# dice.net
KiCad netlist of a schematic drawn in EAGLE
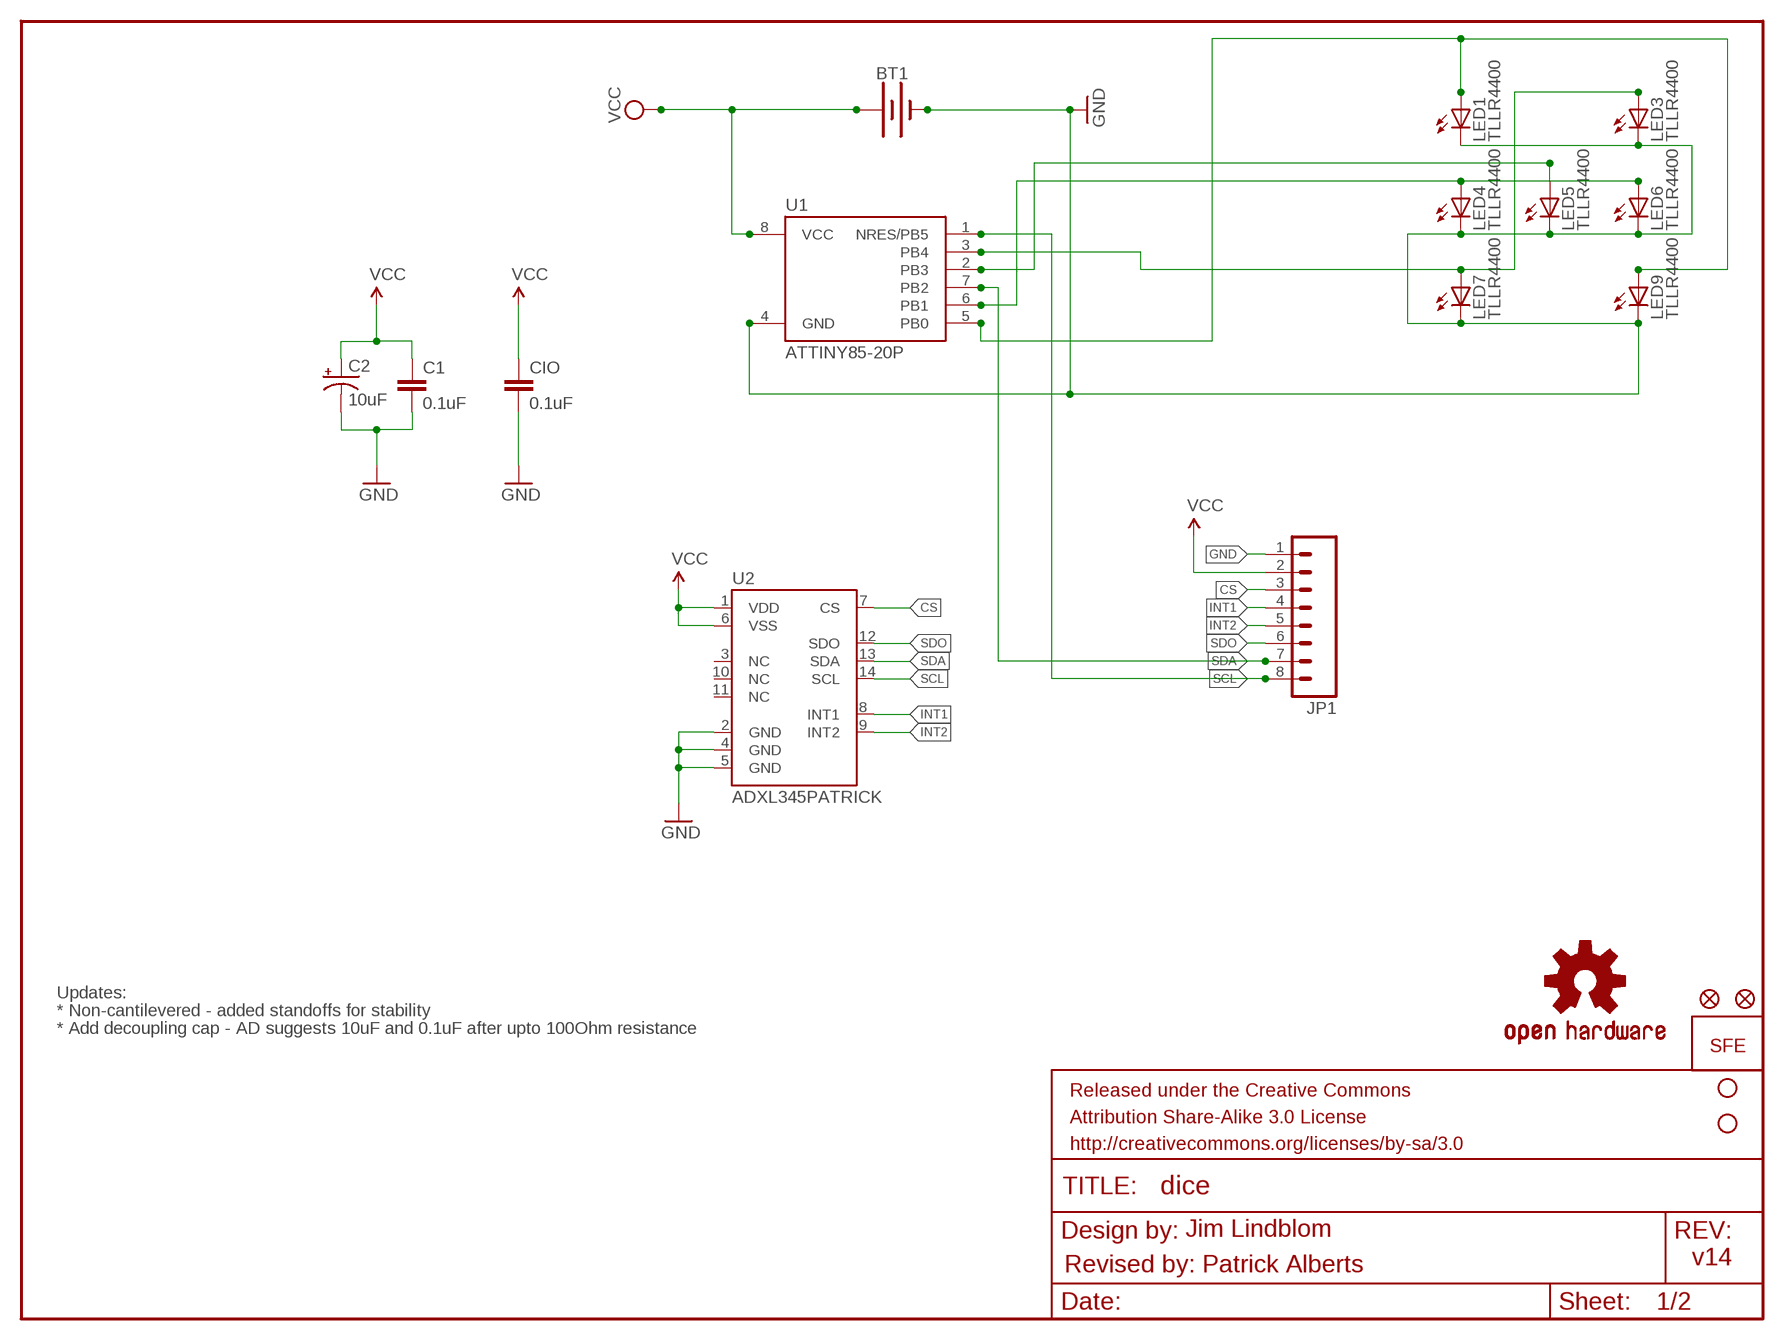
[diagram p0: schematic, sheet 1]

(export (version "E")
  (design (tool "Eeschema 10.0.6"))
  (components
    (comp (ref "BT1")
      (value "BATTERY-20MM_PTH")
      (footprint "eagle-import:BATTCOM_20MM_PTH")
      (libsource (lib "eagle-import") (part "BATTERY-20MM_PTH"))
    )
    (comp (ref "C1")
      (value "0.1uF")
      (footprint "eagle-import:0603-CAP")
      (libsource (lib "eagle-import") (part "CAP0603-CAP"))
    )
    (comp (ref "C2")
      (value "10uF")
      (footprint "eagle-import:EIA3216")
      (libsource (lib "eagle-import") (part "CAP_POL1206"))
    )
    (comp (ref "CIO")
      (value "0.1uF")
      (footprint "eagle-import:0603-CAP")
      (libsource (lib "eagle-import") (part "CAP0603-CAP"))
    )
    (comp (ref "JP1")
      (value "M08")
      (footprint "eagle-import:1X08")
      (libsource (lib "eagle-import") (part "M08"))
    )
    (comp (ref "JP2")
      (value "STAND-OFF")
      (footprint "eagle-import:STAND-OFF")
      (libsource (lib "eagle-import") (part "STAND-OFF"))
    )
    (comp (ref "JP3")
      (value "STAND-OFF")
      (footprint "eagle-import:STAND-OFF")
      (libsource (lib "eagle-import") (part "STAND-OFF"))
    )
    (comp (ref "JP4")
      (value "FIDUCIAL1X2")
      (footprint "eagle-import:FIDUCIAL-1X2")
      (libsource (lib "eagle-import") (part "FIDUCIAL1X2"))
    )
    (comp (ref "JP5")
      (value "FIDUCIAL1X2")
      (footprint "eagle-import:FIDUCIAL-1X2")
      (libsource (lib "eagle-import") (part "FIDUCIAL1X2"))
    )
    (comp (ref "LED1")
      (value "TLLR4400")
      (footprint "eagle-import:LED3MM")
      (fields (field (name "MF") "VISHAY SEMICONDUCTOR"))
      (libsource (lib "eagle-import") (part "TLLR4400"))
    )
    (comp (ref "LED3")
      (value "TLLR4400")
      (footprint "eagle-import:LED3MM")
      (fields (field (name "MF") "VISHAY SEMICONDUCTOR"))
      (libsource (lib "eagle-import") (part "TLLR4400"))
    )
    (comp (ref "LED4")
      (value "TLLR4400")
      (footprint "eagle-import:LED3MM")
      (fields (field (name "MF") "VISHAY SEMICONDUCTOR"))
      (libsource (lib "eagle-import") (part "TLLR4400"))
    )
    (comp (ref "LED5")
      (value "TLLR4400")
      (footprint "eagle-import:LED3MM")
      (fields (field (name "MF") "VISHAY SEMICONDUCTOR"))
      (libsource (lib "eagle-import") (part "TLLR4400"))
    )
    (comp (ref "LED6")
      (value "TLLR4400")
      (footprint "eagle-import:LED3MM")
      (fields (field (name "MF") "VISHAY SEMICONDUCTOR"))
      (libsource (lib "eagle-import") (part "TLLR4400"))
    )
    (comp (ref "LED7")
      (value "TLLR4400")
      (footprint "eagle-import:LED3MM")
      (fields (field (name "MF") "VISHAY SEMICONDUCTOR"))
      (libsource (lib "eagle-import") (part "TLLR4400"))
    )
    (comp (ref "LED9")
      (value "TLLR4400")
      (footprint "eagle-import:LED3MM")
      (fields (field (name "MF") "VISHAY SEMICONDUCTOR"))
      (libsource (lib "eagle-import") (part "TLLR4400"))
    )
    (comp (ref "U$2")
      (value "LOGO-SFENEW")
      (footprint "eagle-import:SFE-NEW-WEBLOGO")
      (libsource (lib "eagle-import") (part "LOGO-SFENEW"))
    )
    (comp (ref "U$3")
      (value "OSHW-LOGOS")
      (footprint "eagle-import:OSHW-LOGO-S")
      (libsource (lib "eagle-import") (part "OSHW-LOGOS"))
    )
    (comp (ref "U1")
      (value "ATTINY85-20P")
      (footprint "eagle-import:PDIP08_300MIL")
      (libsource (lib "eagle-import") (part "ATTINY85P-20"))
    )
    (comp (ref "U2")
      (value "ADXL345PATRICK")
      (footprint "eagle-import:LGA14_1_1_PATRICK")
      (libsource (lib "eagle-import") (part "ADXL345PATRICK"))
    )
  )
  (nets
    (net (code "1") (name "CS") (class "Default")
      (node (ref "JP1") (pin "3") (pinfunction "3_3") (pintype "passive"))
      (node (ref "U2") (pin "7") (pinfunction "CS_7") (pintype "bidirectional"))
    )
    (net (code "2") (name "GND") (class "Default")
      (node (ref "BT1") (pin "2") (pinfunction "-_2") (pintype "power_in"))
      (node (ref "C1") (pin "2") (pinfunction "2_2") (pintype "passive"))
      (node (ref "C2") (pin "C") (pinfunction "-_C") (pintype "passive"))
      (node (ref "CIO") (pin "2") (pinfunction "2_2") (pintype "passive"))
      (node (ref "JP1") (pin "1") (pinfunction "1_1") (pintype "passive"))
      (node (ref "LED1") (pin "K") (pinfunction "C_K") (pintype "passive"))
      (node (ref "LED3") (pin "K") (pinfunction "C_K") (pintype "passive"))
      (node (ref "LED4") (pin "K") (pinfunction "C_K") (pintype "passive"))
      (node (ref "LED5") (pin "K") (pinfunction "C_K") (pintype "passive"))
      (node (ref "LED6") (pin "K") (pinfunction "C_K") (pintype "passive"))
      (node (ref "LED7") (pin "K") (pinfunction "C_K") (pintype "passive"))
      (node (ref "LED9") (pin "K") (pinfunction "C_K") (pintype "passive"))
      (node (ref "U1") (pin "4") (pinfunction "GND_4") (pintype "power_in"))
      (node (ref "U2") (pin "2") (pinfunction "GND_2") (pintype "bidirectional"))
      (node (ref "U2") (pin "4") (pinfunction "GND_4") (pintype "bidirectional"))
      (node (ref "U2") (pin "5") (pinfunction "GND_5") (pintype "bidirectional"))
    )
    (net (code "3") (name "INT1") (class "Default")
      (node (ref "JP1") (pin "4") (pinfunction "4_4") (pintype "passive"))
      (node (ref "U2") (pin "8") (pinfunction "INT1_8") (pintype "bidirectional"))
    )
    (net (code "4") (name "INT2") (class "Default")
      (node (ref "JP1") (pin "5") (pinfunction "5_5") (pintype "passive"))
      (node (ref "U2") (pin "9") (pinfunction "INT2_9") (pintype "bidirectional"))
    )
    (net (code "5") (name "Net-(U1-PB0)") (class "Default")
      (node (ref "LED1") (pin "A") (pinfunction "A_A") (pintype "passive"))
      (node (ref "LED9") (pin "A") (pinfunction "A_A") (pintype "passive"))
      (node (ref "U1") (pin "5") (pinfunction "PB0_5") (pintype "bidirectional"))
    )
    (net (code "6") (name "Net-(U1-PB1)") (class "Default")
      (node (ref "LED4") (pin "A") (pinfunction "A_A") (pintype "passive"))
      (node (ref "LED6") (pin "A") (pinfunction "A_A") (pintype "passive"))
      (node (ref "U1") (pin "6") (pinfunction "PB1_6") (pintype "bidirectional"))
    )
    (net (code "7") (name "Net-(U1-PB3)") (class "Default")
      (node (ref "LED5") (pin "A") (pinfunction "A_A") (pintype "passive"))
      (node (ref "U1") (pin "2") (pinfunction "PB3_2") (pintype "bidirectional"))
    )
    (net (code "8") (name "Net-(U1-PB4)") (class "Default")
      (node (ref "LED3") (pin "A") (pinfunction "A_A") (pintype "passive"))
      (node (ref "LED7") (pin "A") (pinfunction "A_A") (pintype "passive"))
      (node (ref "U1") (pin "3") (pinfunction "PB4_3") (pintype "bidirectional"))
    )
    (net (code "9") (name "SCL") (class "Default")
      (node (ref "JP1") (pin "8") (pinfunction "8_8") (pintype "passive"))
      (node (ref "U1") (pin "1") (pinfunction "NRES/PB5_1") (pintype "bidirectional"))
      (node (ref "U2") (pin "14") (pinfunction "SCL_14") (pintype "bidirectional"))
    )
    (net (code "10") (name "SDA") (class "Default")
      (node (ref "JP1") (pin "7") (pinfunction "7_7") (pintype "passive"))
      (node (ref "U1") (pin "7") (pinfunction "PB2_7") (pintype "bidirectional"))
      (node (ref "U2") (pin "13") (pinfunction "SDA_13") (pintype "bidirectional"))
    )
    (net (code "11") (name "SDO") (class "Default")
      (node (ref "JP1") (pin "6") (pinfunction "6_6") (pintype "passive"))
      (node (ref "U2") (pin "12") (pinfunction "SDO_12") (pintype "bidirectional"))
    )
    (net (code "12") (name "VCC") (class "Default")
      (node (ref "BT1") (pin "1") (pinfunction "+_1") (pintype "power_in"))
      (node (ref "C1") (pin "1") (pinfunction "1_1") (pintype "passive"))
      (node (ref "C2") (pin "A") (pinfunction "+_A") (pintype "passive"))
      (node (ref "CIO") (pin "1") (pinfunction "1_1") (pintype "passive"))
      (node (ref "JP1") (pin "2") (pinfunction "2_2") (pintype "passive"))
      (node (ref "U1") (pin "8") (pinfunction "VCC_8") (pintype "power_in"))
      (node (ref "U2") (pin "1") (pinfunction "VDD_1") (pintype "bidirectional"))
      (node (ref "U2") (pin "6") (pinfunction "VSS_6") (pintype "bidirectional"))
    )
    (net (code "13") (name "unconnected-(U2-NC-Pad3)") (class "Default")
      (node (ref "U2") (pin "3") (pinfunction "NC_3") (pintype "bidirectional"))
    )
    (net (code "14") (name "unconnected-(U2-NC-Pad10)") (class "Default")
      (node (ref "U2") (pin "10") (pinfunction "NC_10") (pintype "bidirectional"))
    )
    (net (code "15") (name "unconnected-(U2-NC-Pad11)") (class "Default")
      (node (ref "U2") (pin "11") (pinfunction "NC_11") (pintype "bidirectional"))
    )
  )
)
